# CNY.net
KiCad netlist of a schematic drawn in Altium Designer
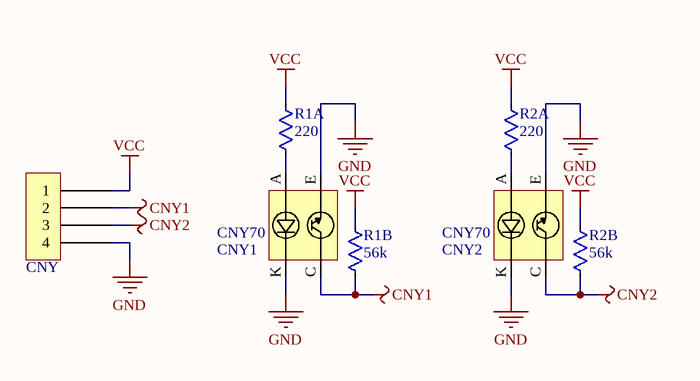
[diagram p0: CNY.SchDoc]

(export (version "E")
  (design (tool "Eeschema 10.0.6"))
  (components
    (comp (ref "CNY")
      (value "Header 1x4")
      (footprint "Header 1x4")
      (libsource (lib "AltiumLibrary") (part "Header 1x4"))
    )
    (comp (ref "CNY1") (value "CNY70") (footprint "CNY70_LIB") (libsource (lib "CNY70") (part "CNY70")))
    (comp (ref "CNY2") (value "CNY70") (footprint "CNY70_LIB") (libsource (lib "CNY70") (part "CNY70")))
    (comp (ref "R1A")
      (value "220")
      (footprint "RES-Axial-400mil")
      (fields (field (name "Comment") "RES"))
      (libsource (lib "AltiumLibrary") (part "RES"))
    )
    (comp (ref "R1B")
      (value "56k")
      (footprint "RES-Axial-400mil")
      (fields (field (name "Comment") "RES"))
      (libsource (lib "AltiumLibrary") (part "RES"))
    )
    (comp (ref "R2A")
      (value "220")
      (footprint "RES-Axial-400mil")
      (fields (field (name "Comment") "RES"))
      (libsource (lib "AltiumLibrary") (part "RES"))
    )
    (comp (ref "R2B")
      (value "56k")
      (footprint "RES-Axial-400mil")
      (fields (field (name "Comment") "RES"))
      (libsource (lib "AltiumLibrary") (part "RES"))
    )
  )
  (nets
    (net (code "1") (name "CNY1") (class "Default")
      (node (ref "CNY") (pin "2") (pinfunction "2_2") (pintype "passive"))
      (node (ref "CNY1") (pin "C") (pinfunction "3_C") (pintype "passive"))
      (node (ref "R1B") (pin "1") (pintype "passive"))
    )
    (net (code "2") (name "CNY2") (class "Default")
      (node (ref "CNY") (pin "3") (pinfunction "3_3") (pintype "passive"))
      (node (ref "CNY2") (pin "C") (pinfunction "3_C") (pintype "passive"))
      (node (ref "R2B") (pin "1") (pintype "passive"))
    )
    (net (code "3") (name "GND") (class "Default")
      (node (ref "CNY") (pin "4") (pinfunction "4_4") (pintype "passive"))
      (node (ref "CNY1") (pin "E") (pinfunction "1_E") (pintype "passive"))
      (node (ref "CNY1") (pin "K") (pinfunction "2_K") (pintype "passive"))
      (node (ref "CNY2") (pin "E") (pinfunction "1_E") (pintype "passive"))
      (node (ref "CNY2") (pin "K") (pinfunction "2_K") (pintype "passive"))
    )
    (net (code "4") (name "Net-(CNY1-0)") (class "Default")
      (node (ref "CNY1") (pin "A") (pinfunction "0_A") (pintype "passive"))
      (node (ref "R1A") (pin "1") (pintype "passive"))
    )
    (net (code "5") (name "Net-(CNY2-0)") (class "Default")
      (node (ref "CNY2") (pin "A") (pinfunction "0_A") (pintype "passive"))
      (node (ref "R2A") (pin "1") (pintype "passive"))
    )
    (net (code "6") (name "VCC") (class "Default")
      (node (ref "CNY") (pin "1") (pinfunction "1_1") (pintype "passive"))
      (node (ref "R1A") (pin "2") (pintype "passive"))
      (node (ref "R1B") (pin "2") (pintype "passive"))
      (node (ref "R2A") (pin "2") (pintype "passive"))
      (node (ref "R2B") (pin "2") (pintype "passive"))
    )
  )
)
